# Peripherals.net
KiCad netlist of a schematic drawn in Altium Designer
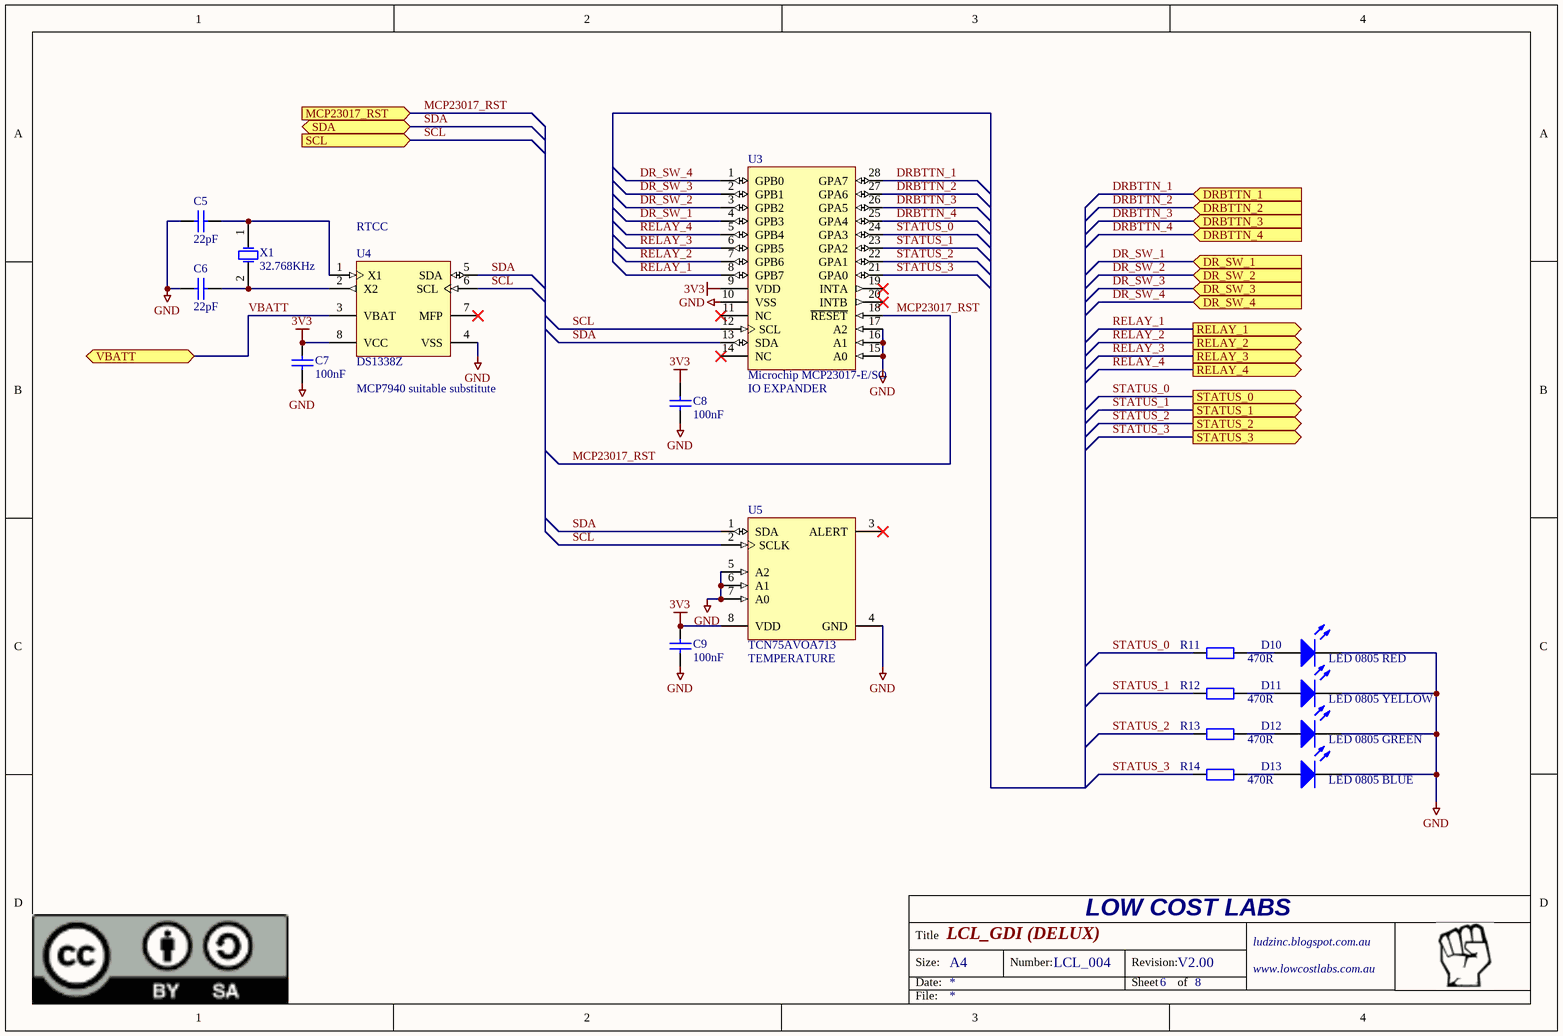
[diagram p0: Peripherals.SchDoc]

(export (version "E")
  (design (tool "Eeschema 10.0.6"))
  (components
    (comp (ref "C5")
      (value "22pF")
      (footprint "PCB-vlqtv48lgr288fxw4eza-1")
      (description "GENERIC 0805 CAPACITOR")
      (libsource (lib "FavoritesLibrary") (part "SYM-hzp74w7y18pxh5z0pr7s-1"))
    )
    (comp (ref "C6")
      (value "22pF")
      (footprint "PCB-vlqtv48lgr288fxw4eza-1")
      (description "GENERIC 0805 CAPACITOR")
      (libsource (lib "FavoritesLibrary") (part "SYM-hzp74w7y18pxh5z0pr7s-1"))
    )
    (comp (ref "C7")
      (value "100nF")
      (footprint "PCB-vlqtv48lgr288fxw4eza-1")
      (description "GENERIC 0805 CAPACITOR")
      (libsource (lib "FavoritesLibrary") (part "SYM-hzp74w7y18pxh5z0pr7s-1"))
    )
    (comp (ref "C8")
      (value "100nF")
      (footprint "PCB-vlqtv48lgr288fxw4eza-1")
      (description "GENERIC 0805 CAPACITOR")
      (libsource (lib "FavoritesLibrary") (part "SYM-hzp74w7y18pxh5z0pr7s-1"))
    )
    (comp (ref "C9")
      (value "100nF")
      (footprint "PCB-vlqtv48lgr288fxw4eza-1")
      (description "GENERIC 0805 CAPACITOR")
      (libsource (lib "FavoritesLibrary") (part "SYM-hzp74w7y18pxh5z0pr7s-1"))
    )
    (comp (ref "D10")
      (value "LED 0805 RED")
      (footprint "PCB-1071566-1")
      (libsource (lib "FavoritesLibrary") (part "SYM-hyfk0d9q8jygmed95nz1-1"))
    )
    (comp (ref "D11")
      (value "LED 0805 YELLOW")
      (footprint "PCB-jd3vqu3yujcdtm6p0xhq-1")
      (libsource (lib "FavoritesLibrary") (part "SYM-jd3vqu3yujcdtm6p0xhq-1"))
    )
    (comp (ref "D12")
      (value "LED 0805 GREEN")
      (footprint "PCB-1071566-1")
      (libsource (lib "FavoritesLibrary") (part "SYM-qw5bzvzxueusztn5titj-1"))
    )
    (comp (ref "D13")
      (value "LED 0805 BLUE")
      (footprint "PCB-kse1vp9j500ix6ujga0m-1")
      (libsource (lib "FavoritesLibrary") (part "SYM-kse1vp9j500ix6ujga0m-1"))
    )
    (comp (ref "R11")
      (value "470R")
      (footprint "PCB-3652081-2")
      (description "GENERIC 0805 RESISTOR")
      (libsource (lib "FavoritesLibrary") (part "SYM-rprrpiwz7au7w5x5ojb2-1"))
    )
    (comp (ref "R12")
      (value "470R")
      (footprint "PCB-3652081-2")
      (description "GENERIC 0805 RESISTOR")
      (libsource (lib "FavoritesLibrary") (part "SYM-rprrpiwz7au7w5x5ojb2-1"))
    )
    (comp (ref "R13")
      (value "470R")
      (footprint "PCB-3652081-2")
      (description "GENERIC 0805 RESISTOR")
      (libsource (lib "FavoritesLibrary") (part "SYM-rprrpiwz7au7w5x5ojb2-1"))
    )
    (comp (ref "R14")
      (value "470R")
      (footprint "PCB-3652081-2")
      (description "GENERIC 0805 RESISTOR")
      (libsource (lib "FavoritesLibrary") (part "SYM-rprrpiwz7au7w5x5ojb2-1"))
    )
    (comp (ref "U3")
      (value "Microchip MCP23017-E/SO")
      (footprint "SOIC-SO28_N")
      (description "MCP23017 Series 5.5 V 1.7 MHz SMT 16-Bit I2C I/O Expander - SOIC-28")
      (fields (field (name "MANUFACTURER PART NUMBER") "MCP23017-E/SO"))
      (libsource (lib "FavoritesLibrary") (part "MCHP-MCP23017-SOIC28"))
    )
    (comp (ref "U4")
      (value "DS1338Z")
      (footprint "SOIC-SN8_N")
      (libsource (lib "CommunityVault") (part "PR-RTC-MCP7940N-8"))
    )
    (comp (ref "U5")
      (value "TCN75AVOA713")
      (footprint "SOIC-OA8_N")
      (description "2-Wire Serial Temperature Sensor, 8-Pin SOIC, Extended Temperature, Tape and Reel")
      (libsource (lib "FavoritesLibrary") (part "SEN-TEMP-MCP980X-8"))
    )
    (comp (ref "X1")
      (value "32.768KHz")
      (footprint "ABRA-AB15T-2_V")
      (libsource (lib "CommunityVault") (part "ABRA-XTAL_1-2-2"))
    )
  )
  (nets
    (net (code "1") (name "/DRBTTN_1") (class "Default")
      (node (ref "U3") (pin "28") (pinfunction "GPA7_28") (pintype "bidirectional"))
    )
    (net (code "2") (name "/DRBTTN_2") (class "Default")
      (node (ref "U3") (pin "27") (pinfunction "GPA6_27") (pintype "bidirectional"))
    )
    (net (code "3") (name "/DRBTTN_3") (class "Default")
      (node (ref "U3") (pin "26") (pinfunction "GPA5_26") (pintype "bidirectional"))
    )
    (net (code "4") (name "/DRBTTN_4") (class "Default")
      (node (ref "U3") (pin "25") (pinfunction "GPA4_25") (pintype "bidirectional"))
    )
    (net (code "5") (name "/DR_SW_1") (class "Default")
      (node (ref "U3") (pin "4") (pinfunction "GPB3_4") (pintype "bidirectional"))
    )
    (net (code "6") (name "/DR_SW_2") (class "Default")
      (node (ref "U3") (pin "3") (pinfunction "GPB2_3") (pintype "bidirectional"))
    )
    (net (code "7") (name "/DR_SW_3") (class "Default")
      (node (ref "U3") (pin "2") (pinfunction "GPB1_2") (pintype "bidirectional"))
    )
    (net (code "8") (name "/DR_SW_4") (class "Default")
      (node (ref "U3") (pin "1") (pinfunction "GPB0_1") (pintype "bidirectional"))
    )
    (net (code "9") (name "/MCP23017_RST") (class "Default")
      (node (ref "U3") (pin "18") (pinfunction "~{RESET}_18") (pintype "input"))
    )
    (net (code "10") (name "/RELAY_1") (class "Default")
      (node (ref "U3") (pin "8") (pinfunction "GPB7_8") (pintype "bidirectional"))
    )
    (net (code "11") (name "/RELAY_2") (class "Default")
      (node (ref "U3") (pin "7") (pinfunction "GPB6_7") (pintype "bidirectional"))
    )
    (net (code "12") (name "/RELAY_3") (class "Default")
      (node (ref "U3") (pin "6") (pinfunction "GPB5_6") (pintype "bidirectional"))
    )
    (net (code "13") (name "/RELAY_4") (class "Default")
      (node (ref "U3") (pin "5") (pinfunction "GPB4_5") (pintype "bidirectional"))
    )
    (net (code "14") (name "/SCL") (class "Default")
      (node (ref "U3") (pin "12") (pinfunction "SCL_12") (pintype "input"))
      (node (ref "U4") (pin "6") (pinfunction "SCL_6") (pintype "input"))
      (node (ref "U5") (pin "2") (pinfunction "SCLK_2") (pintype "input"))
    )
    (net (code "15") (name "/SDA") (class "Default")
      (node (ref "U3") (pin "13") (pinfunction "SDA_13") (pintype "bidirectional"))
      (node (ref "U4") (pin "5") (pinfunction "SDA_5") (pintype "bidirectional"))
      (node (ref "U5") (pin "1") (pinfunction "SDA_1") (pintype "bidirectional"))
    )
    (net (code "16") (name "/STATUS_0") (class "Default")
      (node (ref "R11") (pin "1") (pinfunction "1_1") (pintype "passive"))
      (node (ref "U3") (pin "24") (pinfunction "GPA3_24") (pintype "bidirectional"))
    )
    (net (code "17") (name "/STATUS_1") (class "Default")
      (node (ref "R12") (pin "1") (pinfunction "1_1") (pintype "passive"))
      (node (ref "U3") (pin "23") (pinfunction "GPA2_23") (pintype "bidirectional"))
    )
    (net (code "18") (name "/STATUS_2") (class "Default")
      (node (ref "R13") (pin "1") (pinfunction "1_1") (pintype "passive"))
      (node (ref "U3") (pin "22") (pinfunction "GPA1_22") (pintype "bidirectional"))
    )
    (net (code "19") (name "/STATUS_3") (class "Default")
      (node (ref "R14") (pin "1") (pinfunction "1_1") (pintype "passive"))
      (node (ref "U3") (pin "21") (pinfunction "GPA0_21") (pintype "bidirectional"))
    )
    (net (code "20") (name "/VBATT") (class "Default")
      (node (ref "U4") (pin "3") (pinfunction "VBAT_3") (pintype "power_in"))
    )
    (net (code "21") (name "3V3") (class "Default")
      (node (ref "C7") (pin "2") (pinfunction "2_2") (pintype "passive"))
      (node (ref "C8") (pin "2") (pinfunction "2_2") (pintype "passive"))
      (node (ref "C9") (pin "2") (pinfunction "2_2") (pintype "passive"))
      (node (ref "U3") (pin "9") (pinfunction "VDD_9") (pintype "power_in"))
      (node (ref "U4") (pin "8") (pinfunction "VCC_8") (pintype "power_in"))
      (node (ref "U5") (pin "8") (pinfunction "VDD_8") (pintype "power_in"))
    )
    (net (code "22") (name "GND") (class "Default")
      (node (ref "C5") (pin "1") (pinfunction "1_1") (pintype "passive"))
      (node (ref "C6") (pin "1") (pinfunction "1_1") (pintype "passive"))
      (node (ref "C7") (pin "1") (pinfunction "1_1") (pintype "passive"))
      (node (ref "C8") (pin "1") (pinfunction "1_1") (pintype "passive"))
      (node (ref "C9") (pin "1") (pinfunction "1_1") (pintype "passive"))
      (node (ref "D10") (pin "K") (pinfunction "K_K") (pintype "passive"))
      (node (ref "D11") (pin "K") (pinfunction "K_K") (pintype "passive"))
      (node (ref "D12") (pin "K") (pinfunction "K_K") (pintype "passive"))
      (node (ref "D13") (pin "K") (pinfunction "K_K") (pintype "passive"))
      (node (ref "U3") (pin "10") (pinfunction "VSS_10") (pintype "power_in"))
      (node (ref "U3") (pin "15") (pinfunction "A0_15") (pintype "input"))
      (node (ref "U3") (pin "16") (pinfunction "A1_16") (pintype "input"))
      (node (ref "U3") (pin "17") (pinfunction "A2_17") (pintype "input"))
      (node (ref "U4") (pin "4") (pinfunction "VSS_4") (pintype "power_in"))
      (node (ref "U5") (pin "4") (pinfunction "GND_4") (pintype "power_in"))
      (node (ref "U5") (pin "5") (pinfunction "A2_5") (pintype "input"))
      (node (ref "U5") (pin "6") (pinfunction "A1_6") (pintype "input"))
      (node (ref "U5") (pin "7") (pinfunction "A0_7") (pintype "input"))
    )
    (net (code "23") (name "Net-(D10-PadA)") (class "Default")
      (node (ref "D10") (pin "A") (pinfunction "A_A") (pintype "passive"))
      (node (ref "R11") (pin "2") (pinfunction "2_2") (pintype "passive"))
    )
    (net (code "24") (name "Net-(D11-PadA)") (class "Default")
      (node (ref "D11") (pin "A") (pinfunction "A_A") (pintype "passive"))
      (node (ref "R12") (pin "2") (pinfunction "2_2") (pintype "passive"))
    )
    (net (code "25") (name "Net-(D12-PadA)") (class "Default")
      (node (ref "D12") (pin "A") (pinfunction "A_A") (pintype "passive"))
      (node (ref "R13") (pin "2") (pinfunction "2_2") (pintype "passive"))
    )
    (net (code "26") (name "Net-(D13-PadA)") (class "Default")
      (node (ref "D13") (pin "A") (pinfunction "A_A") (pintype "passive"))
      (node (ref "R14") (pin "2") (pinfunction "2_2") (pintype "passive"))
    )
    (net (code "27") (name "Net-(U4-X1)") (class "Default")
      (node (ref "C5") (pin "2") (pinfunction "2_2") (pintype "passive"))
      (node (ref "U4") (pin "1") (pinfunction "X1_1") (pintype "input"))
      (node (ref "X1") (pin "1") (pinfunction "X1_1") (pintype "passive"))
    )
    (net (code "28") (name "Net-(U4-X2)") (class "Default")
      (node (ref "C6") (pin "2") (pinfunction "2_2") (pintype "passive"))
      (node (ref "U4") (pin "2") (pinfunction "X2_2") (pintype "output"))
      (node (ref "X1") (pin "2") (pinfunction "X2_2") (pintype "passive"))
    )
    (net (code "29") (name "unconnected-(U3-INTA-Pad19)") (class "Default")
      (node (ref "U3") (pin "19") (pinfunction "INTA_19") (pintype "output+no_connect"))
    )
    (net (code "30") (name "unconnected-(U3-INTB-Pad20)") (class "Default")
      (node (ref "U3") (pin "20") (pinfunction "INTB_20") (pintype "output+no_connect"))
    )
    (net (code "31") (name "unconnected-(U3-NC-Pad11)") (class "Default")
      (node (ref "U3") (pin "11") (pinfunction "NC_11") (pintype "passive+no_connect"))
    )
    (net (code "32") (name "unconnected-(U3-NC-Pad14)") (class "Default")
      (node (ref "U3") (pin "14") (pinfunction "NC_14") (pintype "passive+no_connect"))
    )
    (net (code "33") (name "unconnected-(U4-MFP-Pad7)") (class "Default")
      (node (ref "U4") (pin "7") (pinfunction "MFP_7") (pintype "open_collector+no_connect"))
    )
    (net (code "34") (name "unconnected-(U5-ALERT-Pad3)") (class "Default")
      (node (ref "U5") (pin "3") (pinfunction "ALERT_3") (pintype "open_collector+no_connect"))
    )
  )
)
